# Injectors.net
KiCad netlist of a schematic drawn in Altium Designer
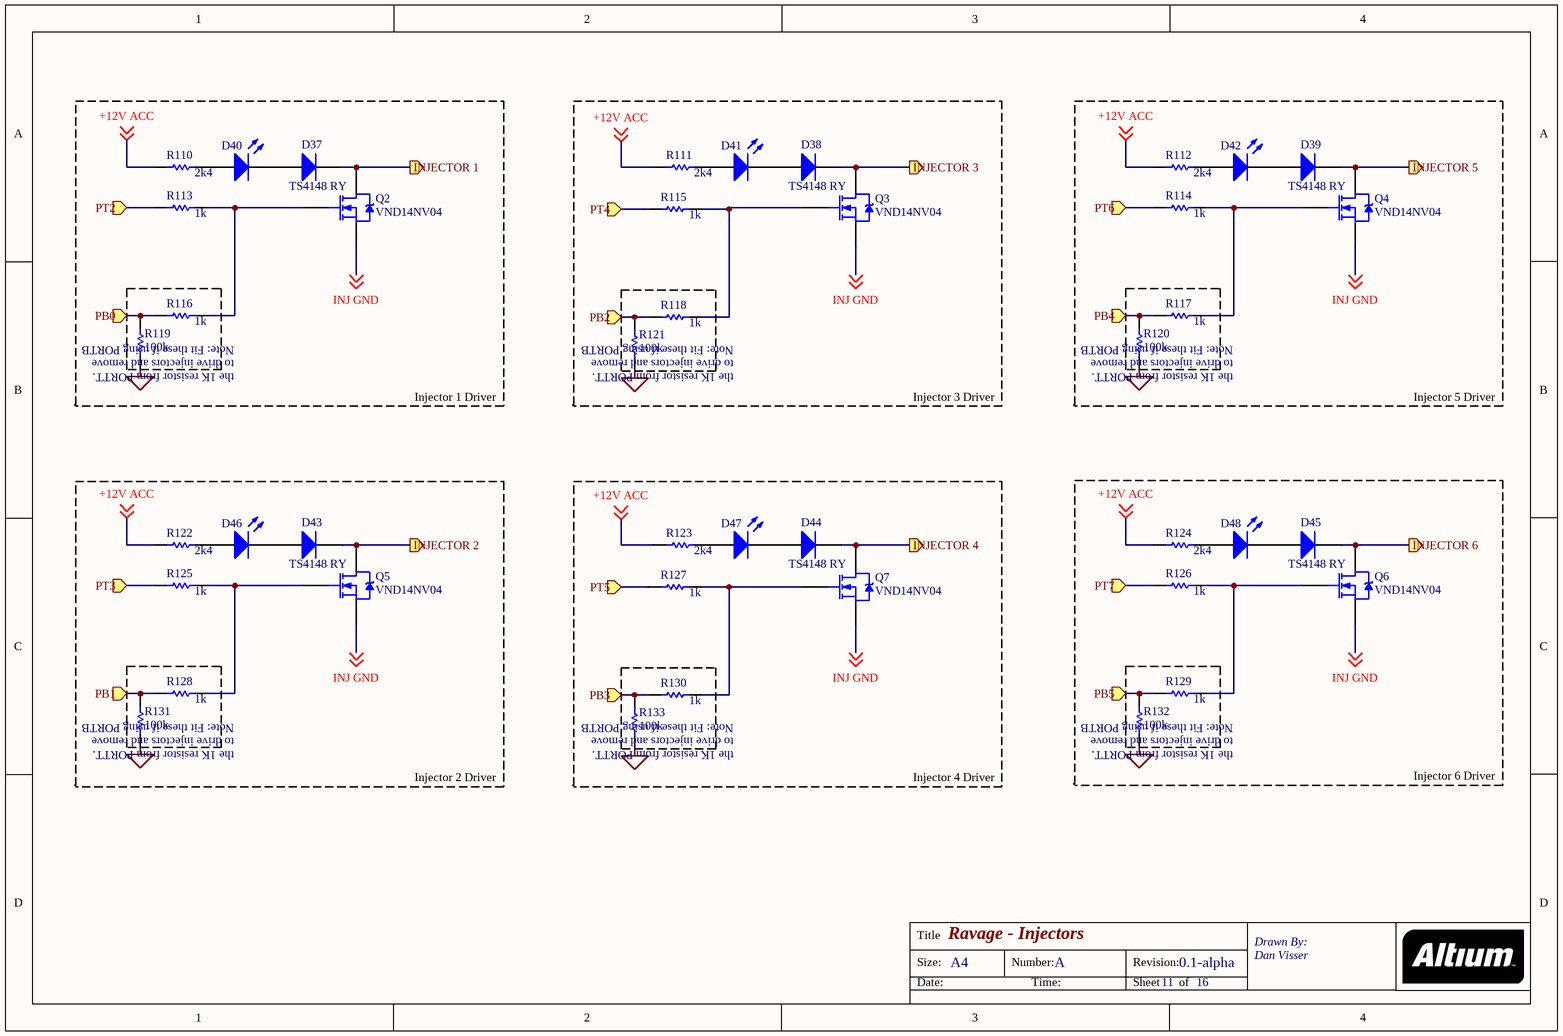
[diagram p0: Injectors.SchDoc]

(export (version "E")
  (design (tool "Eeschema 10.0.6"))
  (components
    (comp (ref "D37")
      (value "TS4148 RY")
      (footprint "SMC")
      (description "Default Diode")
      (fields (field (name "PUBLISHER") "Altium Limited"))
      (libsource (lib "Miscellaneous Devices") (part "Diode"))
    )
    (comp (ref "D38")
      (value "TS4148 RY")
      (footprint "SMC")
      (description "Default Diode")
      (fields (field (name "PUBLISHER") "Altium Limited"))
      (libsource (lib "Miscellaneous Devices") (part "Diode"))
    )
    (comp (ref "D39")
      (value "TS4148 RY")
      (footprint "SMC")
      (description "Default Diode")
      (fields (field (name "PUBLISHER") "Altium Limited"))
      (libsource (lib "Miscellaneous Devices") (part "Diode"))
    )
    (comp (ref "D40")
      (value "~")
      (footprint "LED-0")
      (description "Typical INFRARED GaAs LED")
      (fields (field (name "PUBLISHER") "Altium Limited"))
      (libsource (lib "Miscellaneous Devices") (part "LED0"))
    )
    (comp (ref "D41")
      (value "~")
      (footprint "LED-0")
      (description "Typical INFRARED GaAs LED")
      (fields (field (name "PUBLISHER") "Altium Limited"))
      (libsource (lib "Miscellaneous Devices") (part "LED0"))
    )
    (comp (ref "D42")
      (value "~")
      (footprint "LED-0")
      (description "Typical INFRARED GaAs LED")
      (fields (field (name "PUBLISHER") "Altium Limited"))
      (libsource (lib "Miscellaneous Devices") (part "LED0"))
    )
    (comp (ref "D43")
      (value "TS4148 RY")
      (footprint "SMC")
      (description "Default Diode")
      (fields (field (name "PUBLISHER") "Altium Limited"))
      (libsource (lib "Miscellaneous Devices") (part "Diode"))
    )
    (comp (ref "D44")
      (value "TS4148 RY")
      (footprint "SMC")
      (description "Default Diode")
      (fields (field (name "PUBLISHER") "Altium Limited"))
      (libsource (lib "Miscellaneous Devices") (part "Diode"))
    )
    (comp (ref "D45")
      (value "TS4148 RY")
      (footprint "SMC")
      (description "Default Diode")
      (fields (field (name "PUBLISHER") "Altium Limited"))
      (libsource (lib "Miscellaneous Devices") (part "Diode"))
    )
    (comp (ref "D46")
      (value "~")
      (footprint "LED-0")
      (description "Typical INFRARED GaAs LED")
      (fields (field (name "PUBLISHER") "Altium Limited"))
      (libsource (lib "Miscellaneous Devices") (part "LED0"))
    )
    (comp (ref "D47")
      (value "~")
      (footprint "LED-0")
      (description "Typical INFRARED GaAs LED")
      (fields (field (name "PUBLISHER") "Altium Limited"))
      (libsource (lib "Miscellaneous Devices") (part "LED0"))
    )
    (comp (ref "D48")
      (value "~")
      (footprint "LED-0")
      (description "Typical INFRARED GaAs LED")
      (fields (field (name "PUBLISHER") "Altium Limited"))
      (libsource (lib "Miscellaneous Devices") (part "LED0"))
    )
    (comp (ref "Q2")
      (value "VND14NV04")
      (footprint "TO-220AB")
      (description "HEXFET Power MOSFET")
      (fields (field (name "PUBLISHER") "Altium Limited"))
      (libsource (lib "IR Discrete MOSFET - Power") (part "IRL520N"))
    )
    (comp (ref "Q3")
      (value "VND14NV04")
      (footprint "TO-220AB")
      (description "HEXFET Power MOSFET")
      (fields (field (name "PUBLISHER") "Altium Limited"))
      (libsource (lib "IR Discrete MOSFET - Power") (part "IRL520N"))
    )
    (comp (ref "Q4")
      (value "VND14NV04")
      (footprint "TO-220AB")
      (description "HEXFET Power MOSFET")
      (fields (field (name "PUBLISHER") "Altium Limited"))
      (libsource (lib "IR Discrete MOSFET - Power") (part "IRL520N"))
    )
    (comp (ref "Q5")
      (value "VND14NV04")
      (footprint "TO-220AB")
      (description "HEXFET Power MOSFET")
      (fields (field (name "PUBLISHER") "Altium Limited"))
      (libsource (lib "IR Discrete MOSFET - Power") (part "IRL520N"))
    )
    (comp (ref "Q6")
      (value "VND14NV04")
      (footprint "TO-220AB")
      (description "HEXFET Power MOSFET")
      (fields (field (name "PUBLISHER") "Altium Limited"))
      (libsource (lib "IR Discrete MOSFET - Power") (part "IRL520N"))
    )
    (comp (ref "Q7")
      (value "VND14NV04")
      (footprint "TO-220AB")
      (description "HEXFET Power MOSFET")
      (fields (field (name "PUBLISHER") "Altium Limited"))
      (libsource (lib "IR Discrete MOSFET - Power") (part "IRL520N"))
    )
    (comp (ref "R110")
      (value "2k4")
      (footprint "AXIAL-0.3")
      (description "Resistor")
      (fields (field (name "PUBLISHER") "Altium Limited"))
      (libsource (lib "Miscellaneous Devices") (part "Res1"))
    )
    (comp (ref "R111")
      (value "2k4")
      (footprint "AXIAL-0.3")
      (description "Resistor")
      (fields (field (name "PUBLISHER") "Altium Limited"))
      (libsource (lib "Miscellaneous Devices") (part "Res1"))
    )
    (comp (ref "R112")
      (value "2k4")
      (footprint "AXIAL-0.3")
      (description "Resistor")
      (fields (field (name "PUBLISHER") "Altium Limited"))
      (libsource (lib "Miscellaneous Devices") (part "Res1"))
    )
    (comp (ref "R113")
      (value "1k")
      (footprint "AXIAL-0.3")
      (description "Resistor")
      (fields (field (name "PUBLISHER") "Altium Limited"))
      (libsource (lib "Miscellaneous Devices") (part "Res1"))
    )
    (comp (ref "R114")
      (value "1k")
      (footprint "AXIAL-0.3")
      (description "Resistor")
      (fields (field (name "PUBLISHER") "Altium Limited"))
      (libsource (lib "Miscellaneous Devices") (part "Res1"))
    )
    (comp (ref "R115")
      (value "1k")
      (footprint "AXIAL-0.3")
      (description "Resistor")
      (fields (field (name "PUBLISHER") "Altium Limited"))
      (libsource (lib "Miscellaneous Devices") (part "Res1"))
    )
    (comp (ref "R116")
      (value "1k")
      (footprint "AXIAL-0.3")
      (description "Resistor")
      (fields (field (name "PUBLISHER") "Altium Limited"))
      (libsource (lib "Miscellaneous Devices") (part "Res1"))
    )
    (comp (ref "R117")
      (value "1k")
      (footprint "AXIAL-0.3")
      (description "Resistor")
      (fields (field (name "PUBLISHER") "Altium Limited"))
      (libsource (lib "Miscellaneous Devices") (part "Res1"))
    )
    (comp (ref "R118")
      (value "1k")
      (footprint "AXIAL-0.3")
      (description "Resistor")
      (fields (field (name "PUBLISHER") "Altium Limited"))
      (libsource (lib "Miscellaneous Devices") (part "Res1"))
    )
    (comp (ref "R119")
      (value "100k")
      (footprint "AXIAL-0.3")
      (description "Resistor")
      (fields (field (name "PUBLISHER") "Altium Limited"))
      (libsource (lib "Miscellaneous Devices") (part "Res1"))
    )
    (comp (ref "R120")
      (value "100k")
      (footprint "AXIAL-0.3")
      (description "Resistor")
      (fields (field (name "PUBLISHER") "Altium Limited"))
      (libsource (lib "Miscellaneous Devices") (part "Res1"))
    )
    (comp (ref "R121")
      (value "100k")
      (footprint "AXIAL-0.3")
      (description "Resistor")
      (fields (field (name "PUBLISHER") "Altium Limited"))
      (libsource (lib "Miscellaneous Devices") (part "Res1"))
    )
    (comp (ref "R122")
      (value "2k4")
      (footprint "AXIAL-0.3")
      (description "Resistor")
      (fields (field (name "PUBLISHER") "Altium Limited"))
      (libsource (lib "Miscellaneous Devices") (part "Res1"))
    )
    (comp (ref "R123")
      (value "2k4")
      (footprint "AXIAL-0.3")
      (description "Resistor")
      (fields (field (name "PUBLISHER") "Altium Limited"))
      (libsource (lib "Miscellaneous Devices") (part "Res1"))
    )
    (comp (ref "R124")
      (value "2k4")
      (footprint "AXIAL-0.3")
      (description "Resistor")
      (fields (field (name "PUBLISHER") "Altium Limited"))
      (libsource (lib "Miscellaneous Devices") (part "Res1"))
    )
    (comp (ref "R125")
      (value "1k")
      (footprint "AXIAL-0.3")
      (description "Resistor")
      (fields (field (name "PUBLISHER") "Altium Limited"))
      (libsource (lib "Miscellaneous Devices") (part "Res1"))
    )
    (comp (ref "R126")
      (value "1k")
      (footprint "AXIAL-0.3")
      (description "Resistor")
      (fields (field (name "PUBLISHER") "Altium Limited"))
      (libsource (lib "Miscellaneous Devices") (part "Res1"))
    )
    (comp (ref "R127")
      (value "1k")
      (footprint "AXIAL-0.3")
      (description "Resistor")
      (fields (field (name "PUBLISHER") "Altium Limited"))
      (libsource (lib "Miscellaneous Devices") (part "Res1"))
    )
    (comp (ref "R128")
      (value "1k")
      (footprint "AXIAL-0.3")
      (description "Resistor")
      (fields (field (name "PUBLISHER") "Altium Limited"))
      (libsource (lib "Miscellaneous Devices") (part "Res1"))
    )
    (comp (ref "R129")
      (value "1k")
      (footprint "AXIAL-0.3")
      (description "Resistor")
      (fields (field (name "PUBLISHER") "Altium Limited"))
      (libsource (lib "Miscellaneous Devices") (part "Res1"))
    )
    (comp (ref "R130")
      (value "1k")
      (footprint "AXIAL-0.3")
      (description "Resistor")
      (fields (field (name "PUBLISHER") "Altium Limited"))
      (libsource (lib "Miscellaneous Devices") (part "Res1"))
    )
    (comp (ref "R131")
      (value "100k")
      (footprint "AXIAL-0.3")
      (description "Resistor")
      (fields (field (name "PUBLISHER") "Altium Limited"))
      (libsource (lib "Miscellaneous Devices") (part "Res1"))
    )
    (comp (ref "R132")
      (value "100k")
      (footprint "AXIAL-0.3")
      (description "Resistor")
      (fields (field (name "PUBLISHER") "Altium Limited"))
      (libsource (lib "Miscellaneous Devices") (part "Res1"))
    )
    (comp (ref "R133")
      (value "100k")
      (footprint "AXIAL-0.3")
      (description "Resistor")
      (fields (field (name "PUBLISHER") "Altium Limited"))
      (libsource (lib "Miscellaneous Devices") (part "Res1"))
    )
  )
  (nets
    (net (code "1") (name "+12V ACC") (class "Default")
      (node (ref "R110") (pin "1") (pinfunction "1_1") (pintype "passive"))
      (node (ref "R111") (pin "1") (pinfunction "1_1") (pintype "passive"))
      (node (ref "R112") (pin "1") (pinfunction "1_1") (pintype "passive"))
      (node (ref "R122") (pin "1") (pinfunction "1_1") (pintype "passive"))
      (node (ref "R123") (pin "1") (pinfunction "1_1") (pintype "passive"))
      (node (ref "R124") (pin "1") (pinfunction "1_1") (pintype "passive"))
    )
    (net (code "2") (name "/INJECTOR 1") (class "Default")
      (node (ref "D37") (pin "2") (pinfunction "K_2") (pintype "passive"))
      (node (ref "Q2") (pin "2") (pinfunction "D_2") (pintype "passive"))
    )
    (net (code "3") (name "/INJECTOR 2") (class "Default")
      (node (ref "D43") (pin "2") (pinfunction "K_2") (pintype "passive"))
      (node (ref "Q5") (pin "2") (pinfunction "D_2") (pintype "passive"))
    )
    (net (code "4") (name "/INJECTOR 3") (class "Default")
      (node (ref "D38") (pin "2") (pinfunction "K_2") (pintype "passive"))
      (node (ref "Q3") (pin "2") (pinfunction "D_2") (pintype "passive"))
    )
    (net (code "5") (name "/INJECTOR 4") (class "Default")
      (node (ref "D44") (pin "2") (pinfunction "K_2") (pintype "passive"))
      (node (ref "Q7") (pin "2") (pinfunction "D_2") (pintype "passive"))
    )
    (net (code "6") (name "/INJECTOR 5") (class "Default")
      (node (ref "D39") (pin "2") (pinfunction "K_2") (pintype "passive"))
      (node (ref "Q4") (pin "2") (pinfunction "D_2") (pintype "passive"))
    )
    (net (code "7") (name "/INJECTOR 6") (class "Default")
      (node (ref "D45") (pin "2") (pinfunction "K_2") (pintype "passive"))
      (node (ref "Q6") (pin "2") (pinfunction "D_2") (pintype "passive"))
    )
    (net (code "8") (name "/PB0") (class "Default")
      (node (ref "R116") (pin "1") (pinfunction "1_1") (pintype "passive"))
      (node (ref "R119") (pin "2") (pinfunction "2_2") (pintype "passive"))
    )
    (net (code "9") (name "/PB1") (class "Default")
      (node (ref "R128") (pin "1") (pinfunction "1_1") (pintype "passive"))
      (node (ref "R131") (pin "2") (pinfunction "2_2") (pintype "passive"))
    )
    (net (code "10") (name "/PB2") (class "Default")
      (node (ref "R118") (pin "1") (pinfunction "1_1") (pintype "passive"))
      (node (ref "R121") (pin "2") (pinfunction "2_2") (pintype "passive"))
    )
    (net (code "11") (name "/PB3") (class "Default")
      (node (ref "R130") (pin "1") (pinfunction "1_1") (pintype "passive"))
      (node (ref "R133") (pin "2") (pinfunction "2_2") (pintype "passive"))
    )
    (net (code "12") (name "/PB4") (class "Default")
      (node (ref "R117") (pin "1") (pinfunction "1_1") (pintype "passive"))
      (node (ref "R120") (pin "2") (pinfunction "2_2") (pintype "passive"))
    )
    (net (code "13") (name "/PB5") (class "Default")
      (node (ref "R129") (pin "1") (pinfunction "1_1") (pintype "passive"))
      (node (ref "R132") (pin "2") (pinfunction "2_2") (pintype "passive"))
    )
    (net (code "14") (name "/PT2") (class "Default")
      (node (ref "R113") (pin "1") (pinfunction "1_1") (pintype "passive"))
    )
    (net (code "15") (name "/PT3") (class "Default")
      (node (ref "R125") (pin "1") (pinfunction "1_1") (pintype "passive"))
    )
    (net (code "16") (name "/PT4") (class "Default")
      (node (ref "R115") (pin "1") (pinfunction "1_1") (pintype "passive"))
    )
    (net (code "17") (name "/PT5") (class "Default")
      (node (ref "R127") (pin "1") (pinfunction "1_1") (pintype "passive"))
    )
    (net (code "18") (name "/PT6") (class "Default")
      (node (ref "R114") (pin "1") (pinfunction "1_1") (pintype "passive"))
    )
    (net (code "19") (name "/PT7") (class "Default")
      (node (ref "R126") (pin "1") (pinfunction "1_1") (pintype "passive"))
    )
    (net (code "20") (name "<NO NET>") (class "Default")
      (node (ref "R119") (pin "1") (pinfunction "1_1") (pintype "passive"))
      (node (ref "R120") (pin "1") (pinfunction "1_1") (pintype "passive"))
      (node (ref "R121") (pin "1") (pinfunction "1_1") (pintype "passive"))
      (node (ref "R131") (pin "1") (pinfunction "1_1") (pintype "passive"))
      (node (ref "R132") (pin "1") (pinfunction "1_1") (pintype "passive"))
      (node (ref "R133") (pin "1") (pinfunction "1_1") (pintype "passive"))
    )
    (net (code "21") (name "INJ GND") (class "Default")
      (node (ref "Q2") (pin "3") (pinfunction "S_3") (pintype "passive"))
      (node (ref "Q3") (pin "3") (pinfunction "S_3") (pintype "passive"))
      (node (ref "Q4") (pin "3") (pinfunction "S_3") (pintype "passive"))
      (node (ref "Q5") (pin "3") (pinfunction "S_3") (pintype "passive"))
      (node (ref "Q6") (pin "3") (pinfunction "S_3") (pintype "passive"))
      (node (ref "Q7") (pin "3") (pinfunction "S_3") (pintype "passive"))
    )
    (net (code "22") (name "Net-(D37-A)") (class "Default")
      (node (ref "D37") (pin "1") (pinfunction "A_1") (pintype "passive"))
      (node (ref "D40") (pin "2") (pinfunction "K_2") (pintype "passive"))
    )
    (net (code "23") (name "Net-(D38-A)") (class "Default")
      (node (ref "D38") (pin "1") (pinfunction "A_1") (pintype "passive"))
      (node (ref "D41") (pin "2") (pinfunction "K_2") (pintype "passive"))
    )
    (net (code "24") (name "Net-(D39-A)") (class "Default")
      (node (ref "D39") (pin "1") (pinfunction "A_1") (pintype "passive"))
      (node (ref "D42") (pin "2") (pinfunction "K_2") (pintype "passive"))
    )
    (net (code "25") (name "Net-(D40-A)") (class "Default")
      (node (ref "D40") (pin "1") (pinfunction "A_1") (pintype "passive"))
      (node (ref "R110") (pin "2") (pinfunction "2_2") (pintype "passive"))
    )
    (net (code "26") (name "Net-(D41-A)") (class "Default")
      (node (ref "D41") (pin "1") (pinfunction "A_1") (pintype "passive"))
      (node (ref "R111") (pin "2") (pinfunction "2_2") (pintype "passive"))
    )
    (net (code "27") (name "Net-(D42-A)") (class "Default")
      (node (ref "D42") (pin "1") (pinfunction "A_1") (pintype "passive"))
      (node (ref "R112") (pin "2") (pinfunction "2_2") (pintype "passive"))
    )
    (net (code "28") (name "Net-(D43-A)") (class "Default")
      (node (ref "D43") (pin "1") (pinfunction "A_1") (pintype "passive"))
      (node (ref "D46") (pin "2") (pinfunction "K_2") (pintype "passive"))
    )
    (net (code "29") (name "Net-(D44-A)") (class "Default")
      (node (ref "D44") (pin "1") (pinfunction "A_1") (pintype "passive"))
      (node (ref "D47") (pin "2") (pinfunction "K_2") (pintype "passive"))
    )
    (net (code "30") (name "Net-(D45-A)") (class "Default")
      (node (ref "D45") (pin "1") (pinfunction "A_1") (pintype "passive"))
      (node (ref "D48") (pin "2") (pinfunction "K_2") (pintype "passive"))
    )
    (net (code "31") (name "Net-(D46-A)") (class "Default")
      (node (ref "D46") (pin "1") (pinfunction "A_1") (pintype "passive"))
      (node (ref "R122") (pin "2") (pinfunction "2_2") (pintype "passive"))
    )
    (net (code "32") (name "Net-(D47-A)") (class "Default")
      (node (ref "D47") (pin "1") (pinfunction "A_1") (pintype "passive"))
      (node (ref "R123") (pin "2") (pinfunction "2_2") (pintype "passive"))
    )
    (net (code "33") (name "Net-(D48-A)") (class "Default")
      (node (ref "D48") (pin "1") (pinfunction "A_1") (pintype "passive"))
      (node (ref "R124") (pin "2") (pinfunction "2_2") (pintype "passive"))
    )
    (net (code "34") (name "Net-(Q2-G)") (class "Default")
      (node (ref "Q2") (pin "1") (pinfunction "G_1") (pintype "passive"))
      (node (ref "R113") (pin "2") (pinfunction "2_2") (pintype "passive"))
      (node (ref "R116") (pin "2") (pinfunction "2_2") (pintype "passive"))
    )
    (net (code "35") (name "Net-(Q3-G)") (class "Default")
      (node (ref "Q3") (pin "1") (pinfunction "G_1") (pintype "passive"))
      (node (ref "R115") (pin "2") (pinfunction "2_2") (pintype "passive"))
      (node (ref "R118") (pin "2") (pinfunction "2_2") (pintype "passive"))
    )
    (net (code "36") (name "Net-(Q4-G)") (class "Default")
      (node (ref "Q4") (pin "1") (pinfunction "G_1") (pintype "passive"))
      (node (ref "R114") (pin "2") (pinfunction "2_2") (pintype "passive"))
      (node (ref "R117") (pin "2") (pinfunction "2_2") (pintype "passive"))
    )
    (net (code "37") (name "Net-(Q5-G)") (class "Default")
      (node (ref "Q5") (pin "1") (pinfunction "G_1") (pintype "passive"))
      (node (ref "R125") (pin "2") (pinfunction "2_2") (pintype "passive"))
      (node (ref "R128") (pin "2") (pinfunction "2_2") (pintype "passive"))
    )
    (net (code "38") (name "Net-(Q6-G)") (class "Default")
      (node (ref "Q6") (pin "1") (pinfunction "G_1") (pintype "passive"))
      (node (ref "R126") (pin "2") (pinfunction "2_2") (pintype "passive"))
      (node (ref "R129") (pin "2") (pinfunction "2_2") (pintype "passive"))
    )
    (net (code "39") (name "Net-(Q7-G)") (class "Default")
      (node (ref "Q7") (pin "1") (pinfunction "G_1") (pintype "passive"))
      (node (ref "R127") (pin "2") (pinfunction "2_2") (pintype "passive"))
      (node (ref "R130") (pin "2") (pinfunction "2_2") (pintype "passive"))
    )
  )
)
